# 4Bit_Computer_-_1_5LED_Display.net
KiCad netlist of a schematic drawn in EAGLE
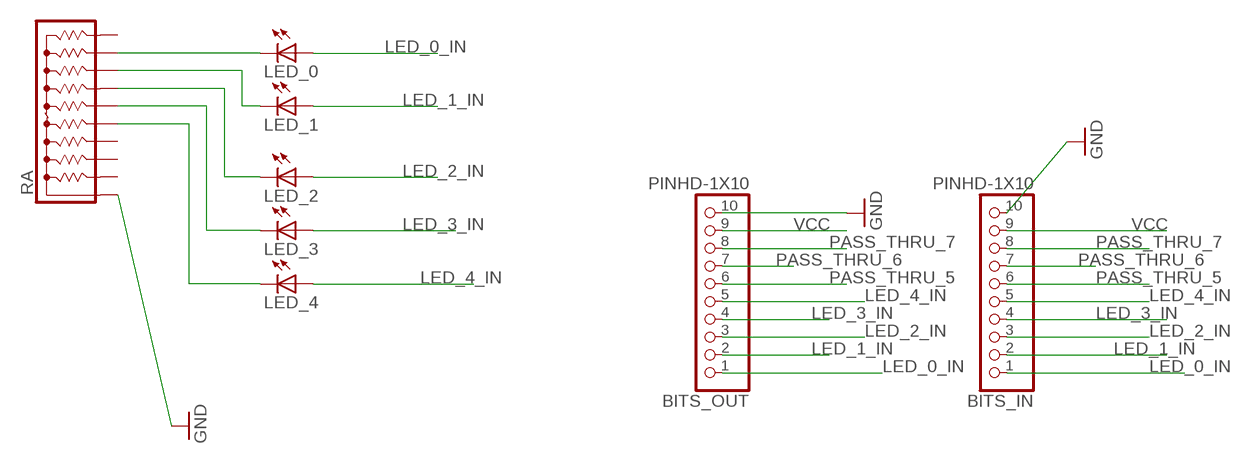
[diagram p0: schematic, sheet 1]

(export (version "E")
  (design (tool "Eeschema 10.0.6"))
  (components
    (comp (ref "BITS_IN")
      (value "PINHD-1X10")
      (footprint "eagle-import:1X10-BIG")
      (libsource (lib "eagle-import") (part "PINHD-1X10"))
    )
    (comp (ref "BITS_OUT")
      (value "PINHD-1X10")
      (footprint "eagle-import:1X10-BIG")
      (libsource (lib "eagle-import") (part "PINHD-1X10"))
    )
    (comp (ref "LED_0")
      (value "LEDSMT1206")
      (footprint "eagle-import:1206")
      (libsource (lib "eagle-import") (part "LEDSMT1206"))
    )
    (comp (ref "LED_1")
      (value "LEDSMT1206")
      (footprint "eagle-import:1206")
      (libsource (lib "eagle-import") (part "LEDSMT1206"))
    )
    (comp (ref "LED_2")
      (value "LEDSMT1206")
      (footprint "eagle-import:1206")
      (libsource (lib "eagle-import") (part "LEDSMT1206"))
    )
    (comp (ref "LED_3")
      (value "LEDSMT1206")
      (footprint "eagle-import:1206")
      (libsource (lib "eagle-import") (part "LEDSMT1206"))
    )
    (comp (ref "LED_4")
      (value "LEDSMT1206")
      (footprint "eagle-import:1206")
      (libsource (lib "eagle-import") (part "LEDSMT1206"))
    )
    (comp (ref "RA")
      (value "4610X")
      (footprint "eagle-import:SIP10")
      (libsource (lib "eagle-import") (part "4610X"))
    )
  )
  (nets
    (net (code "1") (name "/LED_0_IN") (class "Default")
      (node (ref "BITS_IN") (pin "1") (pinfunction "1_1") (pintype "passive"))
      (node (ref "BITS_OUT") (pin "1") (pinfunction "1_1") (pintype "passive"))
      (node (ref "LED_0") (pin "A") (pinfunction "A_A") (pintype "passive"))
    )
    (net (code "2") (name "/LED_1_IN") (class "Default")
      (node (ref "BITS_IN") (pin "2") (pinfunction "2_2") (pintype "passive"))
      (node (ref "BITS_OUT") (pin "2") (pinfunction "2_2") (pintype "passive"))
      (node (ref "LED_1") (pin "A") (pinfunction "A_A") (pintype "passive"))
    )
    (net (code "3") (name "/LED_2_IN") (class "Default")
      (node (ref "BITS_IN") (pin "3") (pinfunction "3_3") (pintype "passive"))
      (node (ref "BITS_OUT") (pin "3") (pinfunction "3_3") (pintype "passive"))
      (node (ref "LED_2") (pin "A") (pinfunction "A_A") (pintype "passive"))
    )
    (net (code "4") (name "/LED_3_IN") (class "Default")
      (node (ref "BITS_IN") (pin "4") (pinfunction "4_4") (pintype "passive"))
      (node (ref "BITS_OUT") (pin "4") (pinfunction "4_4") (pintype "passive"))
      (node (ref "LED_3") (pin "A") (pinfunction "A_A") (pintype "passive"))
    )
    (net (code "5") (name "/LED_4_IN") (class "Default")
      (node (ref "BITS_IN") (pin "5") (pinfunction "5_5") (pintype "passive"))
      (node (ref "BITS_OUT") (pin "5") (pinfunction "5_5") (pintype "passive"))
      (node (ref "LED_4") (pin "A") (pinfunction "A_A") (pintype "passive"))
    )
    (net (code "6") (name "/PASS_THRU_5") (class "Default")
      (node (ref "BITS_IN") (pin "6") (pinfunction "6_6") (pintype "passive"))
      (node (ref "BITS_OUT") (pin "6") (pinfunction "6_6") (pintype "passive"))
    )
    (net (code "7") (name "/PASS_THRU_6") (class "Default")
      (node (ref "BITS_IN") (pin "7") (pinfunction "7_7") (pintype "passive"))
      (node (ref "BITS_OUT") (pin "7") (pinfunction "7_7") (pintype "passive"))
    )
    (net (code "8") (name "/PASS_THRU_7") (class "Default")
      (node (ref "BITS_IN") (pin "8") (pinfunction "8_8") (pintype "passive"))
      (node (ref "BITS_OUT") (pin "8") (pinfunction "8_8") (pintype "passive"))
    )
    (net (code "9") (name "/VCC") (class "Default")
      (node (ref "BITS_IN") (pin "9") (pinfunction "9_9") (pintype "passive"))
      (node (ref "BITS_OUT") (pin "9") (pinfunction "9_9") (pintype "passive"))
    )
    (net (code "10") (name "GND") (class "Default")
      (node (ref "BITS_IN") (pin "10") (pinfunction "10_10") (pintype "passive"))
      (node (ref "BITS_OUT") (pin "10") (pinfunction "10_10") (pintype "passive"))
      (node (ref "RA") (pin "1") (pinfunction "1_1") (pintype "passive"))
    )
    (net (code "11") (name "Net-(LED_0-PadC)") (class "Default")
      (node (ref "LED_0") (pin "C") (pinfunction "C_C") (pintype "passive"))
      (node (ref "RA") (pin "9") (pinfunction "9_9") (pintype "passive"))
    )
    (net (code "12") (name "Net-(LED_1-PadC)") (class "Default")
      (node (ref "LED_1") (pin "C") (pinfunction "C_C") (pintype "passive"))
      (node (ref "RA") (pin "8") (pinfunction "8_8") (pintype "passive"))
    )
    (net (code "13") (name "Net-(LED_2-PadC)") (class "Default")
      (node (ref "LED_2") (pin "C") (pinfunction "C_C") (pintype "passive"))
      (node (ref "RA") (pin "7") (pinfunction "7_7") (pintype "passive"))
    )
    (net (code "14") (name "Net-(LED_3-PadC)") (class "Default")
      (node (ref "LED_3") (pin "C") (pinfunction "C_C") (pintype "passive"))
      (node (ref "RA") (pin "6") (pinfunction "6_6") (pintype "passive"))
    )
    (net (code "15") (name "Net-(LED_4-PadC)") (class "Default")
      (node (ref "LED_4") (pin "C") (pinfunction "C_C") (pintype "passive"))
      (node (ref "RA") (pin "5") (pinfunction "5_5") (pintype "passive"))
    )
    (net (code "16") (name "unconnected-(RA-Pad2)") (class "Default")
      (node (ref "RA") (pin "2") (pinfunction "2_2") (pintype "passive"))
    )
    (net (code "17") (name "unconnected-(RA-Pad3)") (class "Default")
      (node (ref "RA") (pin "3") (pinfunction "3_3") (pintype "passive"))
    )
    (net (code "18") (name "unconnected-(RA-Pad4)") (class "Default")
      (node (ref "RA") (pin "4") (pinfunction "4_4") (pintype "passive"))
    )
    (net (code "19") (name "unconnected-(RA-Pad10)") (class "Default")
      (node (ref "RA") (pin "10") (pinfunction "10_10") (pintype "passive"))
    )
  )
)
